# CaravanPi_V3.net
KiCad netlist of a schematic drawn in EAGLE
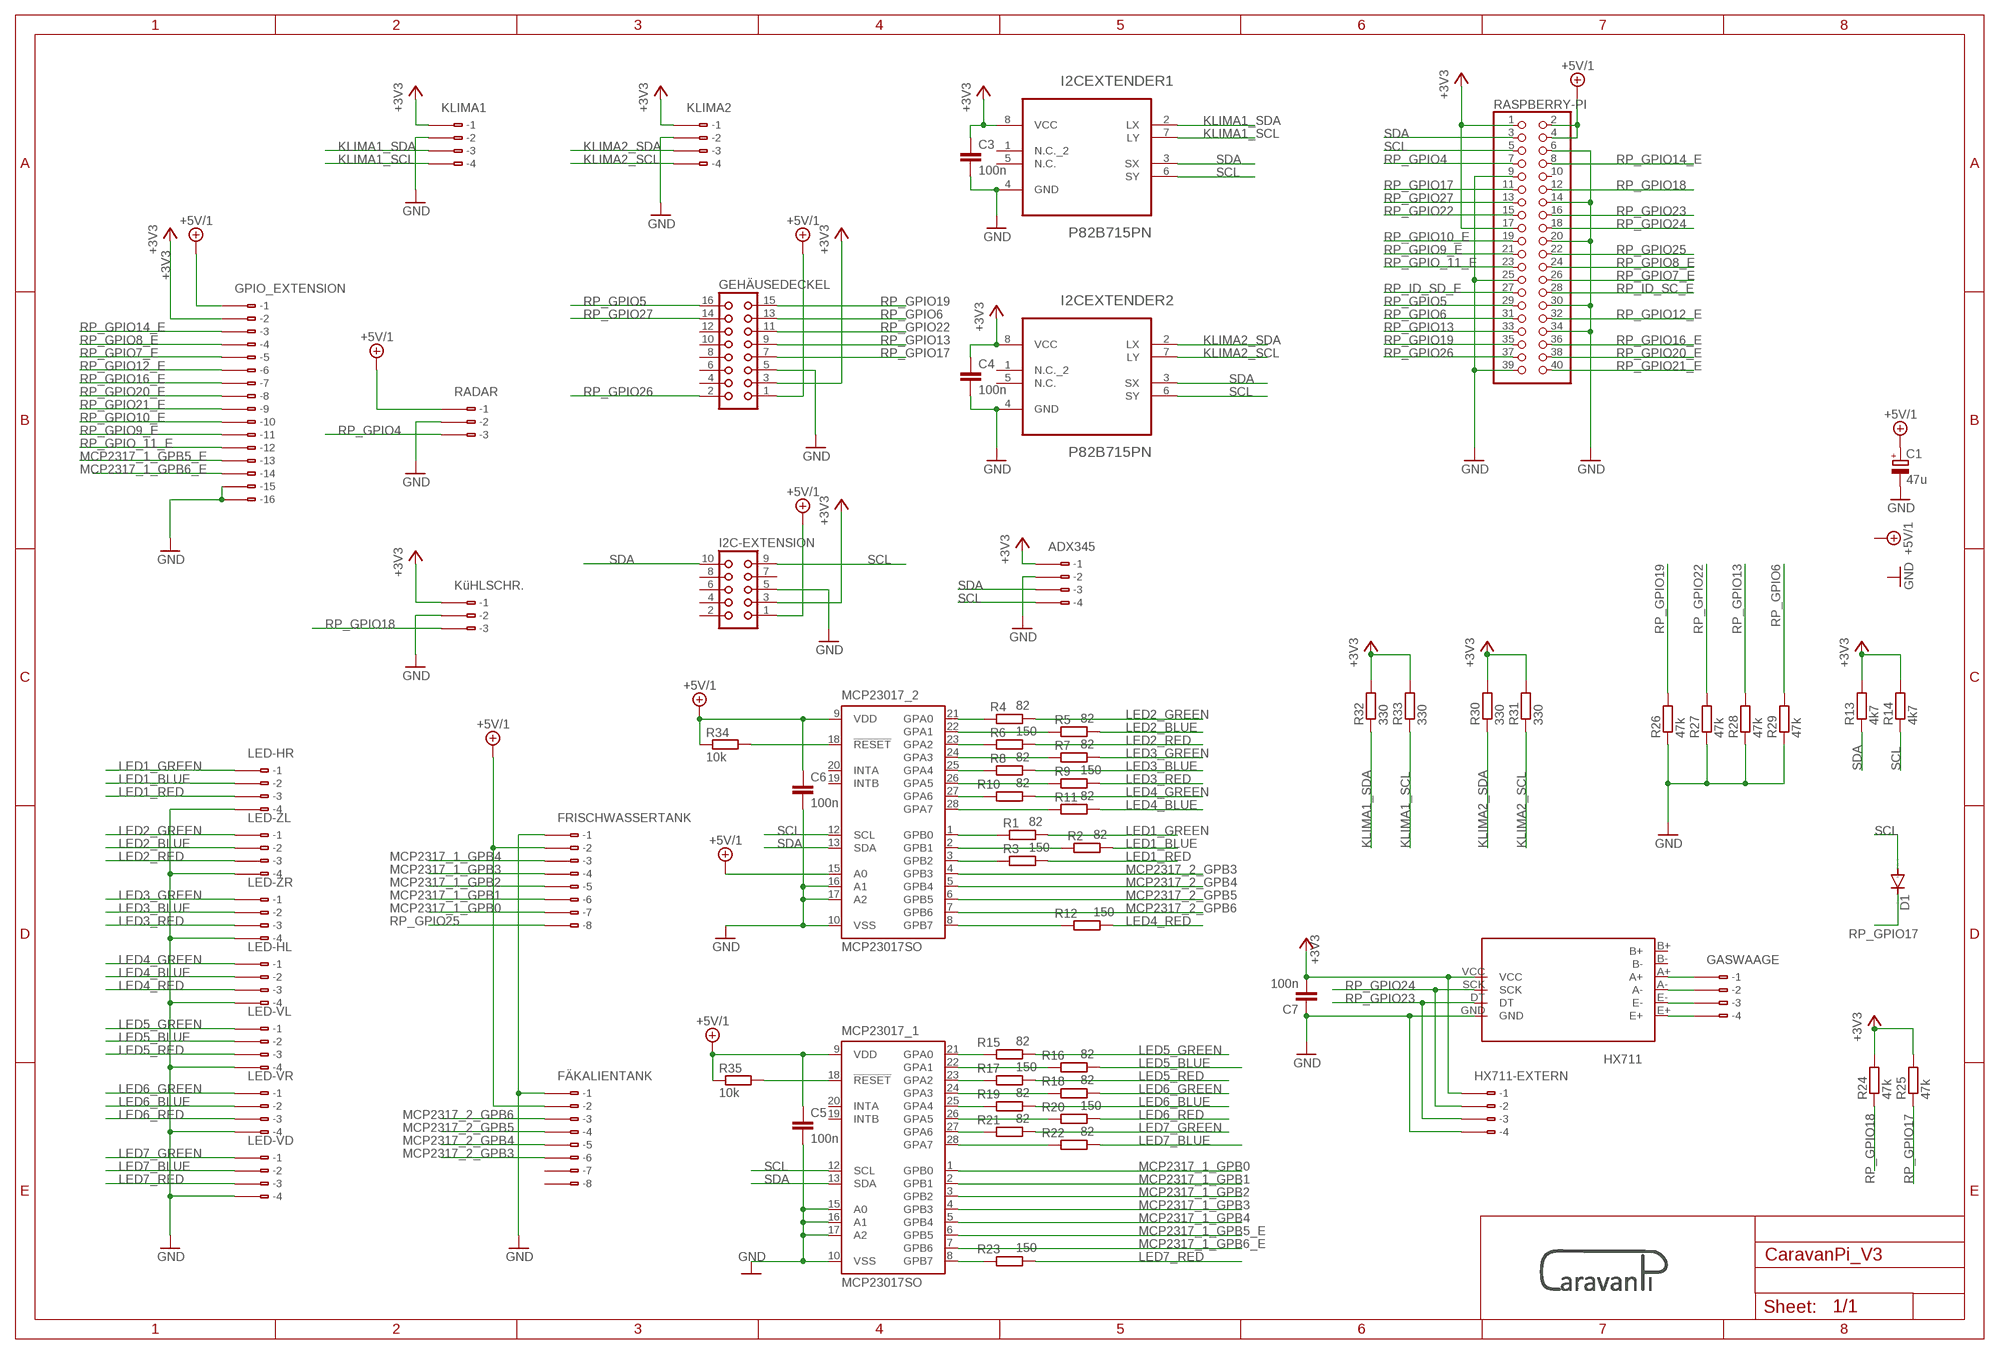
[diagram p0: schematic, sheet 1]

(export (version "E")
  (design (tool "Eeschema 10.0.6"))
  (components
    (comp (ref "ADX345")
      (value "233-404")
      (footprint "eagle-import:233-404")
      (libsource (lib "eagle-import") (part "233-404"))
    )
    (comp (ref "C1")
      (value "47u")
      (footprint "eagle-import:SMC_C")
      (libsource (lib "eagle-import") (part "CPOL-EUSMCC"))
    )
    (comp (ref "C3")
      (value "100n")
      (footprint "eagle-import:C1206")
      (libsource (lib "eagle-import") (part "C-EUC1206"))
    )
    (comp (ref "C4")
      (value "100n")
      (footprint "eagle-import:C1206")
      (libsource (lib "eagle-import") (part "C-EUC1206"))
    )
    (comp (ref "C5")
      (value "100n")
      (footprint "eagle-import:C1206")
      (libsource (lib "eagle-import") (part "C-EUC1206"))
    )
    (comp (ref "C6")
      (value "100n")
      (footprint "eagle-import:C1206")
      (libsource (lib "eagle-import") (part "C-EUC1206"))
    )
    (comp (ref "C7")
      (value "100n")
      (footprint "eagle-import:C1206")
      (libsource (lib "eagle-import") (part "C-EUC1206"))
    )
    (comp (ref "D1")
      (value "DIODE-DO214AC")
      (footprint "eagle-import:DO214AC")
      (libsource (lib "eagle-import") (part "DIODE-DO214AC"))
    )
    (comp (ref "FRISCHWASSERTANK")
      (value "233-408")
      (footprint "eagle-import:233-408")
      (libsource (lib "eagle-import") (part "233-408"))
    )
    (comp (ref "FÄKALIENTANK")
      (value "233-408")
      (footprint "eagle-import:233-408")
      (libsource (lib "eagle-import") (part "233-408"))
    )
    (comp (ref "GASWAAGE")
      (value "233-404")
      (footprint "eagle-import:233-404")
      (libsource (lib "eagle-import") (part "233-404"))
    )
    (comp (ref "GEHÄUSEDECKEL")
      (value "CON16")
      (footprint "eagle-import:CON16")
      (libsource (lib "eagle-import") (part "CON16"))
    )
    (comp (ref "GPIO_EXTENSION")
      (value "233-516")
      (footprint "eagle-import:233-516")
      (fields (field (name "MF") "Wago Corporation") (field (name "MPN") "0233-0516"))
      (libsource (lib "eagle-import") (part "233-516"))
    )
    (comp (ref "HX711")
      (value "HX711A")
      (footprint "eagle-import:HX711")
      (libsource (lib "eagle-import") (part "HX711A"))
    )
    (comp (ref "HX711-EXTERN")
      (value "233-404")
      (footprint "eagle-import:233-404")
      (libsource (lib "eagle-import") (part "233-404"))
    )
    (comp (ref "I2C-EXTENSION")
      (value "CON10")
      (footprint "eagle-import:CON10")
      (libsource (lib "eagle-import") (part "CON10"))
    )
    (comp (ref "I2CEXTENDER1")
      (value "P82B715PN")
      (footprint "eagle-import:DIP254P762X420-8")
      (libsource (lib "eagle-import") (part "P82B715PN"))
    )
    (comp (ref "I2CEXTENDER2")
      (value "P82B715PN")
      (footprint "eagle-import:DIP254P762X420-8")
      (libsource (lib "eagle-import") (part "P82B715PN"))
    )
    (comp (ref "KLIMA1")
      (value "233-404")
      (footprint "eagle-import:233-404")
      (libsource (lib "eagle-import") (part "233-404"))
    )
    (comp (ref "KLIMA2")
      (value "233-404")
      (footprint "eagle-import:233-404")
      (libsource (lib "eagle-import") (part "233-404"))
    )
    (comp (ref "KüHLSCHR.")
      (value "233-403")
      (footprint "eagle-import:233-403")
      (libsource (lib "eagle-import") (part "233-403"))
    )
    (comp (ref "LED-HL")
      (value "233-504")
      (footprint "eagle-import:233-504")
      (fields (field (name "MF") "Wago Corporation") (field (name "MPN") "0233-0504"))
      (libsource (lib "eagle-import") (part "233-504"))
    )
    (comp (ref "LED-HR")
      (value "233-504")
      (footprint "eagle-import:233-504")
      (fields (field (name "MF") "Wago Corporation") (field (name "MPN") "0233-0504"))
      (libsource (lib "eagle-import") (part "233-504"))
    )
    (comp (ref "LED-VD")
      (value "233-504")
      (footprint "eagle-import:233-504")
      (fields (field (name "MF") "Wago Corporation") (field (name "MPN") "0233-0504"))
      (libsource (lib "eagle-import") (part "233-504"))
    )
    (comp (ref "LED-VL")
      (value "233-504")
      (footprint "eagle-import:233-504")
      (fields (field (name "MF") "Wago Corporation") (field (name "MPN") "0233-0504"))
      (libsource (lib "eagle-import") (part "233-504"))
    )
    (comp (ref "LED-VR")
      (value "233-504")
      (footprint "eagle-import:233-504")
      (fields (field (name "MF") "Wago Corporation") (field (name "MPN") "0233-0504"))
      (libsource (lib "eagle-import") (part "233-504"))
    )
    (comp (ref "LED-ZL")
      (value "233-504")
      (footprint "eagle-import:233-504")
      (fields (field (name "MF") "Wago Corporation") (field (name "MPN") "0233-0504"))
      (libsource (lib "eagle-import") (part "233-504"))
    )
    (comp (ref "LED-ZR")
      (value "233-504")
      (footprint "eagle-import:233-504")
      (fields (field (name "MF") "Wago Corporation") (field (name "MPN") "0233-0504"))
      (libsource (lib "eagle-import") (part "233-504"))
    )
    (comp (ref "MCP23017_1")
      (value "MCP23017SO")
      (footprint "eagle-import:SO28W")
      (libsource (lib "eagle-import") (part "MCP23017SO"))
    )
    (comp (ref "MCP23017_2")
      (value "MCP23017SO")
      (footprint "eagle-import:SO28W")
      (libsource (lib "eagle-import") (part "MCP23017SO"))
    )
    (comp (ref "R1")
      (value "82")
      (footprint "eagle-import:M1206")
      (libsource (lib "eagle-import") (part "R-EU_M1206"))
    )
    (comp (ref "R2")
      (value "82")
      (footprint "eagle-import:M1206")
      (libsource (lib "eagle-import") (part "R-EU_M1206"))
    )
    (comp (ref "R3")
      (value "150")
      (footprint "eagle-import:M1206")
      (libsource (lib "eagle-import") (part "R-EU_M1206"))
    )
    (comp (ref "R4")
      (value "82")
      (footprint "eagle-import:M1206")
      (libsource (lib "eagle-import") (part "R-EU_M1206"))
    )
    (comp (ref "R5")
      (value "82")
      (footprint "eagle-import:M1206")
      (libsource (lib "eagle-import") (part "R-EU_M1206"))
    )
    (comp (ref "R6")
      (value "150")
      (footprint "eagle-import:M1206")
      (libsource (lib "eagle-import") (part "R-EU_M1206"))
    )
    (comp (ref "R7")
      (value "82")
      (footprint "eagle-import:M1206")
      (libsource (lib "eagle-import") (part "R-EU_M1206"))
    )
    (comp (ref "R8")
      (value "82")
      (footprint "eagle-import:M1206")
      (libsource (lib "eagle-import") (part "R-EU_M1206"))
    )
    (comp (ref "R9")
      (value "150")
      (footprint "eagle-import:M1206")
      (libsource (lib "eagle-import") (part "R-EU_M1206"))
    )
    (comp (ref "R10")
      (value "82")
      (footprint "eagle-import:M1206")
      (libsource (lib "eagle-import") (part "R-EU_M1206"))
    )
    (comp (ref "R11")
      (value "82")
      (footprint "eagle-import:M1206")
      (libsource (lib "eagle-import") (part "R-EU_M1206"))
    )
    (comp (ref "R12")
      (value "150")
      (footprint "eagle-import:M1206")
      (libsource (lib "eagle-import") (part "R-EU_M1206"))
    )
    (comp (ref "R13")
      (value "4k7")
      (footprint "eagle-import:M1206")
      (libsource (lib "eagle-import") (part "R-EU_M1206"))
    )
    (comp (ref "R14")
      (value "4k7")
      (footprint "eagle-import:M1206")
      (libsource (lib "eagle-import") (part "R-EU_M1206"))
    )
    (comp (ref "R15")
      (value "82")
      (footprint "eagle-import:M1206")
      (libsource (lib "eagle-import") (part "R-EU_M1206"))
    )
    (comp (ref "R16")
      (value "82")
      (footprint "eagle-import:M1206")
      (libsource (lib "eagle-import") (part "R-EU_M1206"))
    )
    (comp (ref "R17")
      (value "150")
      (footprint "eagle-import:M1206")
      (libsource (lib "eagle-import") (part "R-EU_M1206"))
    )
    (comp (ref "R18")
      (value "82")
      (footprint "eagle-import:M1206")
      (libsource (lib "eagle-import") (part "R-EU_M1206"))
    )
    (comp (ref "R19")
      (value "82")
      (footprint "eagle-import:M1206")
      (libsource (lib "eagle-import") (part "R-EU_M1206"))
    )
    (comp (ref "R20")
      (value "150")
      (footprint "eagle-import:M1206")
      (libsource (lib "eagle-import") (part "R-EU_M1206"))
    )
    (comp (ref "R21")
      (value "82")
      (footprint "eagle-import:M1206")
      (libsource (lib "eagle-import") (part "R-EU_M1206"))
    )
    (comp (ref "R22")
      (value "82")
      (footprint "eagle-import:M1206")
      (libsource (lib "eagle-import") (part "R-EU_M1206"))
    )
    (comp (ref "R23")
      (value "150")
      (footprint "eagle-import:M1206")
      (libsource (lib "eagle-import") (part "R-EU_M1206"))
    )
    (comp (ref "R24")
      (value "47k")
      (footprint "eagle-import:M1206")
      (libsource (lib "eagle-import") (part "R-EU_M1206"))
    )
    (comp (ref "R25")
      (value "47k")
      (footprint "eagle-import:M1206")
      (libsource (lib "eagle-import") (part "R-EU_M1206"))
    )
    (comp (ref "R26")
      (value "47k")
      (footprint "eagle-import:M1206")
      (libsource (lib "eagle-import") (part "R-EU_M1206"))
    )
    (comp (ref "R27")
      (value "47k")
      (footprint "eagle-import:M1206")
      (libsource (lib "eagle-import") (part "R-EU_M1206"))
    )
    (comp (ref "R28")
      (value "47k")
      (footprint "eagle-import:M1206")
      (libsource (lib "eagle-import") (part "R-EU_M1206"))
    )
    (comp (ref "R29")
      (value "47k")
      (footprint "eagle-import:M1206")
      (libsource (lib "eagle-import") (part "R-EU_M1206"))
    )
    (comp (ref "R30")
      (value "330")
      (footprint "eagle-import:M1206")
      (libsource (lib "eagle-import") (part "R-EU_M1206"))
    )
    (comp (ref "R31")
      (value "330")
      (footprint "eagle-import:M1206")
      (libsource (lib "eagle-import") (part "R-EU_M1206"))
    )
    (comp (ref "R32")
      (value "330")
      (footprint "eagle-import:M1206")
      (libsource (lib "eagle-import") (part "R-EU_M1206"))
    )
    (comp (ref "R33")
      (value "330")
      (footprint "eagle-import:M1206")
      (libsource (lib "eagle-import") (part "R-EU_M1206"))
    )
    (comp (ref "R34")
      (value "10k")
      (footprint "eagle-import:M1206")
      (libsource (lib "eagle-import") (part "R-EU_M1206"))
    )
    (comp (ref "R35")
      (value "10k")
      (footprint "eagle-import:M1206")
      (libsource (lib "eagle-import") (part "R-EU_M1206"))
    )
    (comp (ref "RADAR")
      (value "233-403")
      (footprint "eagle-import:233-403")
      (libsource (lib "eagle-import") (part "233-403"))
    )
    (comp (ref "RASPBERRY-PI")
      (value "PINHD-2X20")
      (footprint "eagle-import:2X20")
      (libsource (lib "eagle-import") (part "PINHD-2X20"))
    )
    (comp (ref "U$1")
      (value "CARAVAN_PI_LOGO")
      (footprint "eagle-import:CARAVAN_PI_LOGO")
      (libsource (lib "eagle-import") (part "CARAVAN_PI_LOGO"))
    )
  )
  (nets
    (net (code "1") (name "+3V3") (class "Default")
      (node (ref "ADX345") (pin "B1") (pinfunction "B-1_B1") (pintype "passive"))
      (node (ref "C3") (pin "1") (pinfunction "1_1") (pintype "passive"))
      (node (ref "C4") (pin "1") (pinfunction "1_1") (pintype "passive"))
      (node (ref "C7") (pin "2") (pinfunction "2_2") (pintype "passive"))
      (node (ref "GEHÄUSEDECKEL") (pin "3") (pinfunction "3_3") (pintype "passive"))
      (node (ref "GPIO_EXTENSION") (pin "B2") (pinfunction "B-2_B2") (pintype "passive"))
      (node (ref "HX711") (pin "VCC") (pinfunction "VCC_VCC") (pintype "bidirectional"))
      (node (ref "HX711-EXTERN") (pin "B1") (pinfunction "B-1_B1") (pintype "passive"))
      (node (ref "I2C-EXTENSION") (pin "3") (pinfunction "3_3") (pintype "passive"))
      (node (ref "I2CEXTENDER1") (pin "8") (pinfunction "VCC_8") (pintype "power_in"))
      (node (ref "I2CEXTENDER2") (pin "8") (pinfunction "VCC_8") (pintype "power_in"))
      (node (ref "KLIMA1") (pin "B1") (pinfunction "B-1_B1") (pintype "passive"))
      (node (ref "KLIMA2") (pin "B1") (pinfunction "B-1_B1") (pintype "passive"))
      (node (ref "KüHLSCHR.") (pin "B1") (pinfunction "B-1_B1") (pintype "passive"))
      (node (ref "R13") (pin "2") (pinfunction "2_2") (pintype "passive"))
      (node (ref "R14") (pin "2") (pinfunction "2_2") (pintype "passive"))
      (node (ref "R24") (pin "2") (pinfunction "2_2") (pintype "passive"))
      (node (ref "R25") (pin "2") (pinfunction "2_2") (pintype "passive"))
      (node (ref "R30") (pin "2") (pinfunction "2_2") (pintype "passive"))
      (node (ref "R31") (pin "2") (pinfunction "2_2") (pintype "passive"))
      (node (ref "R32") (pin "2") (pinfunction "2_2") (pintype "passive"))
      (node (ref "R33") (pin "2") (pinfunction "2_2") (pintype "passive"))
      (node (ref "RASPBERRY-PI") (pin "1") (pinfunction "1_1") (pintype "passive"))
      (node (ref "RASPBERRY-PI") (pin "17") (pinfunction "17_17") (pintype "passive"))
    )
    (net (code "2") (name "+5V{slash}1") (class "Default")
      (node (ref "C1") (pin "+") (pinfunction "+_+") (pintype "passive"))
      (node (ref "C5") (pin "1") (pinfunction "1_1") (pintype "passive"))
      (node (ref "C6") (pin "1") (pinfunction "1_1") (pintype "passive"))
      (node (ref "FRISCHWASSERTANK") (pin "B2") (pinfunction "B-2_B2") (pintype "passive"))
      (node (ref "FÄKALIENTANK") (pin "B2") (pinfunction "B-2_B2") (pintype "passive"))
      (node (ref "GEHÄUSEDECKEL") (pin "1") (pinfunction "1_1") (pintype "passive"))
      (node (ref "GPIO_EXTENSION") (pin "B1") (pinfunction "B-1_B1") (pintype "passive"))
      (node (ref "I2C-EXTENSION") (pin "1") (pinfunction "1_1") (pintype "passive"))
      (node (ref "MCP23017_1") (pin "9") (pinfunction "VDD_9") (pintype "power_in"))
      (node (ref "MCP23017_2") (pin "15") (pinfunction "A0_15") (pintype "input"))
      (node (ref "MCP23017_2") (pin "9") (pinfunction "VDD_9") (pintype "power_in"))
      (node (ref "R34") (pin "1") (pinfunction "1_1") (pintype "passive"))
      (node (ref "R35") (pin "1") (pinfunction "1_1") (pintype "passive"))
      (node (ref "RADAR") (pin "B1") (pinfunction "B-1_B1") (pintype "passive"))
      (node (ref "RASPBERRY-PI") (pin "2") (pinfunction "2_2") (pintype "passive"))
      (node (ref "RASPBERRY-PI") (pin "4") (pinfunction "4_4") (pintype "passive"))
    )
    (net (code "3") (name "/KLIMA1_SCL") (class "Default")
      (node (ref "I2CEXTENDER1") (pin "7") (pinfunction "LY_7") (pintype "bidirectional"))
      (node (ref "KLIMA1") (pin "B4") (pinfunction "B-4_B4") (pintype "passive"))
      (node (ref "R33") (pin "1") (pinfunction "1_1") (pintype "passive"))
    )
    (net (code "4") (name "/KLIMA1_SDA") (class "Default")
      (node (ref "I2CEXTENDER1") (pin "2") (pinfunction "LX_2") (pintype "bidirectional"))
      (node (ref "KLIMA1") (pin "B3") (pinfunction "B-3_B3") (pintype "passive"))
      (node (ref "R32") (pin "1") (pinfunction "1_1") (pintype "passive"))
    )
    (net (code "5") (name "/KLIMA2_SCL") (class "Default")
      (node (ref "I2CEXTENDER2") (pin "7") (pinfunction "LY_7") (pintype "bidirectional"))
      (node (ref "KLIMA2") (pin "B4") (pinfunction "B-4_B4") (pintype "passive"))
      (node (ref "R31") (pin "1") (pinfunction "1_1") (pintype "passive"))
    )
    (net (code "6") (name "/KLIMA2_SDA") (class "Default")
      (node (ref "I2CEXTENDER2") (pin "2") (pinfunction "LX_2") (pintype "bidirectional"))
      (node (ref "KLIMA2") (pin "B3") (pinfunction "B-3_B3") (pintype "passive"))
      (node (ref "R30") (pin "1") (pinfunction "1_1") (pintype "passive"))
    )
    (net (code "7") (name "/LED1_BLUE") (class "Default")
      (node (ref "LED-HR") (pin "B2") (pinfunction "B-2_B2") (pintype "passive"))
      (node (ref "R2") (pin "2") (pinfunction "2_2") (pintype "passive"))
    )
    (net (code "8") (name "/LED1_GREEN") (class "Default")
      (node (ref "LED-HR") (pin "B1") (pinfunction "B-1_B1") (pintype "passive"))
      (node (ref "R1") (pin "2") (pinfunction "2_2") (pintype "passive"))
    )
    (net (code "9") (name "/LED1_RED") (class "Default")
      (node (ref "LED-HR") (pin "B3") (pinfunction "B-3_B3") (pintype "passive"))
      (node (ref "R3") (pin "2") (pinfunction "2_2") (pintype "passive"))
    )
    (net (code "10") (name "/LED2_BLUE") (class "Default")
      (node (ref "LED-ZL") (pin "B2") (pinfunction "B-2_B2") (pintype "passive"))
      (node (ref "R5") (pin "2") (pinfunction "2_2") (pintype "passive"))
    )
    (net (code "11") (name "/LED2_GREEN") (class "Default")
      (node (ref "LED-ZL") (pin "B1") (pinfunction "B-1_B1") (pintype "passive"))
      (node (ref "R4") (pin "2") (pinfunction "2_2") (pintype "passive"))
    )
    (net (code "12") (name "/LED2_RED") (class "Default")
      (node (ref "LED-ZL") (pin "B3") (pinfunction "B-3_B3") (pintype "passive"))
      (node (ref "R6") (pin "2") (pinfunction "2_2") (pintype "passive"))
    )
    (net (code "13") (name "/LED3_BLUE") (class "Default")
      (node (ref "LED-ZR") (pin "B2") (pinfunction "B-2_B2") (pintype "passive"))
      (node (ref "R8") (pin "2") (pinfunction "2_2") (pintype "passive"))
    )
    (net (code "14") (name "/LED3_GREEN") (class "Default")
      (node (ref "LED-ZR") (pin "B1") (pinfunction "B-1_B1") (pintype "passive"))
      (node (ref "R7") (pin "2") (pinfunction "2_2") (pintype "passive"))
    )
    (net (code "15") (name "/LED3_RED") (class "Default")
      (node (ref "LED-ZR") (pin "B3") (pinfunction "B-3_B3") (pintype "passive"))
      (node (ref "R9") (pin "2") (pinfunction "2_2") (pintype "passive"))
    )
    (net (code "16") (name "/LED4_BLUE") (class "Default")
      (node (ref "LED-HL") (pin "B2") (pinfunction "B-2_B2") (pintype "passive"))
      (node (ref "R11") (pin "2") (pinfunction "2_2") (pintype "passive"))
    )
    (net (code "17") (name "/LED4_GREEN") (class "Default")
      (node (ref "LED-HL") (pin "B1") (pinfunction "B-1_B1") (pintype "passive"))
      (node (ref "R10") (pin "2") (pinfunction "2_2") (pintype "passive"))
    )
    (net (code "18") (name "/LED4_RED") (class "Default")
      (node (ref "LED-HL") (pin "B3") (pinfunction "B-3_B3") (pintype "passive"))
      (node (ref "R12") (pin "2") (pinfunction "2_2") (pintype "passive"))
    )
    (net (code "19") (name "/LED5_BLUE") (class "Default")
      (node (ref "LED-VL") (pin "B2") (pinfunction "B-2_B2") (pintype "passive"))
      (node (ref "R16") (pin "2") (pinfunction "2_2") (pintype "passive"))
    )
    (net (code "20") (name "/LED5_GREEN") (class "Default")
      (node (ref "LED-VL") (pin "B1") (pinfunction "B-1_B1") (pintype "passive"))
      (node (ref "R15") (pin "2") (pinfunction "2_2") (pintype "passive"))
    )
    (net (code "21") (name "/LED5_RED") (class "Default")
      (node (ref "LED-VL") (pin "B3") (pinfunction "B-3_B3") (pintype "passive"))
      (node (ref "R17") (pin "2") (pinfunction "2_2") (pintype "passive"))
    )
    (net (code "22") (name "/LED6_BLUE") (class "Default")
      (node (ref "LED-VR") (pin "B2") (pinfunction "B-2_B2") (pintype "passive"))
      (node (ref "R19") (pin "2") (pinfunction "2_2") (pintype "passive"))
    )
    (net (code "23") (name "/LED6_GREEN") (class "Default")
      (node (ref "LED-VR") (pin "B1") (pinfunction "B-1_B1") (pintype "passive"))
      (node (ref "R18") (pin "2") (pinfunction "2_2") (pintype "passive"))
    )
    (net (code "24") (name "/LED6_RED") (class "Default")
      (node (ref "LED-VR") (pin "B3") (pinfunction "B-3_B3") (pintype "passive"))
      (node (ref "R20") (pin "2") (pinfunction "2_2") (pintype "passive"))
    )
    (net (code "25") (name "/LED7_BLUE") (class "Default")
      (node (ref "LED-VD") (pin "B2") (pinfunction "B-2_B2") (pintype "passive"))
      (node (ref "R22") (pin "2") (pinfunction "2_2") (pintype "passive"))
    )
    (net (code "26") (name "/LED7_GREEN") (class "Default")
      (node (ref "LED-VD") (pin "B1") (pinfunction "B-1_B1") (pintype "passive"))
      (node (ref "R21") (pin "2") (pinfunction "2_2") (pintype "passive"))
    )
    (net (code "27") (name "/LED7_RED") (class "Default")
      (node (ref "LED-VD") (pin "B3") (pinfunction "B-3_B3") (pintype "passive"))
      (node (ref "R23") (pin "2") (pinfunction "2_2") (pintype "passive"))
    )
    (net (code "28") (name "/MCP2317_1_GPB0") (class "Default")
      (node (ref "FRISCHWASSERTANK") (pin "B7") (pinfunction "B-7_B7") (pintype "passive"))
      (node (ref "MCP23017_1") (pin "1") (pinfunction "GPB0_1") (pintype "bidirectional"))
    )
    (net (code "29") (name "/MCP2317_1_GPB1") (class "Default")
      (node (ref "FRISCHWASSERTANK") (pin "B6") (pinfunction "B-6_B6") (pintype "passive"))
      (node (ref "MCP23017_1") (pin "2") (pinfunction "GPB1_2") (pintype "bidirectional"))
    )
    (net (code "30") (name "/MCP2317_1_GPB2") (class "Default")
      (node (ref "FRISCHWASSERTANK") (pin "B5") (pinfunction "B-5_B5") (pintype "passive"))
      (node (ref "MCP23017_1") (pin "3") (pinfunction "GPB2_3") (pintype "bidirectional"))
    )
    (net (code "31") (name "/MCP2317_1_GPB3") (class "Default")
      (node (ref "FRISCHWASSERTANK") (pin "B4") (pinfunction "B-4_B4") (pintype "passive"))
      (node (ref "MCP23017_1") (pin "4") (pinfunction "GPB3_4") (pintype "bidirectional"))
    )
    (net (code "32") (name "/MCP2317_1_GPB4") (class "Default")
      (node (ref "FRISCHWASSERTANK") (pin "B3") (pinfunction "B-3_B3") (pintype "passive"))
      (node (ref "MCP23017_1") (pin "5") (pinfunction "GPB4_5") (pintype "bidirectional"))
    )
    (net (code "33") (name "/MCP2317_1_GPB5_E") (class "Default")
      (node (ref "GPIO_EXTENSION") (pin "B13") (pinfunction "B-13_B13") (pintype "passive"))
      (node (ref "MCP23017_1") (pin "6") (pinfunction "GPB5_6") (pintype "bidirectional"))
    )
    (net (code "34") (name "/MCP2317_1_GPB6_E") (class "Default")
      (node (ref "GPIO_EXTENSION") (pin "B14") (pinfunction "B-14_B14") (pintype "passive"))
      (node (ref "MCP23017_1") (pin "7") (pinfunction "GPB6_7") (pintype "bidirectional"))
    )
    (net (code "35") (name "/MCP2317_2_GPB3") (class "Default")
      (node (ref "FÄKALIENTANK") (pin "B6") (pinfunction "B-6_B6") (pintype "passive"))
      (node (ref "MCP23017_2") (pin "4") (pinfunction "GPB3_4") (pintype "bidirectional"))
    )
    (net (code "36") (name "/MCP2317_2_GPB4") (class "Default")
      (node (ref "FÄKALIENTANK") (pin "B5") (pinfunction "B-5_B5") (pintype "passive"))
      (node (ref "MCP23017_2") (pin "5") (pinfunction "GPB4_5") (pintype "bidirectional"))
    )
    (net (code "37") (name "/MCP2317_2_GPB5") (class "Default")
      (node (ref "FÄKALIENTANK") (pin "B4") (pinfunction "B-4_B4") (pintype "passive"))
      (node (ref "MCP23017_2") (pin "6") (pinfunction "GPB5_6") (pintype "bidirectional"))
    )
    (net (code "38") (name "/MCP2317_2_GPB6") (class "Default")
      (node (ref "FÄKALIENTANK") (pin "B3") (pinfunction "B-3_B3") (pintype "passive"))
      (node (ref "MCP23017_2") (pin "7") (pinfunction "GPB6_7") (pintype "bidirectional"))
    )
    (net (code "39") (name "/RP_GPIO4") (class "Default")
      (node (ref "RADAR") (pin "B3") (pinfunction "B-3_B3") (pintype "passive"))
      (node (ref "RASPBERRY-PI") (pin "7") (pinfunction "7_7") (pintype "passive"))
    )
    (net (code "40") (name "/RP_GPIO5") (class "Default")
      (node (ref "GEHÄUSEDECKEL") (pin "16") (pinfunction "16_16") (pintype "passive"))
      (node (ref "RASPBERRY-PI") (pin "29") (pinfunction "29_29") (pintype "passive"))
    )
    (net (code "41") (name "/RP_GPIO6") (class "Default")
      (node (ref "GEHÄUSEDECKEL") (pin "13") (pinfunction "13_13") (pintype "passive"))
      (node (ref "R29") (pin "2") (pinfunction "2_2") (pintype "passive"))
      (node (ref "RASPBERRY-PI") (pin "31") (pinfunction "31_31") (pintype "passive"))
    )
    (net (code "42") (name "/RP_GPIO7_E") (class "Default")
      (node (ref "GPIO_EXTENSION") (pin "B5") (pinfunction "B-5_B5") (pintype "passive"))
      (node (ref "RASPBERRY-PI") (pin "26") (pinfunction "26_26") (pintype "passive"))
    )
    (net (code "43") (name "/RP_GPIO8_E") (class "Default")
      (node (ref "GPIO_EXTENSION") (pin "B4") (pinfunction "B-4_B4") (pintype "passive"))
      (node (ref "RASPBERRY-PI") (pin "24") (pinfunction "24_24") (pintype "passive"))
    )
    (net (code "44") (name "/RP_GPIO9_E") (class "Default")
      (node (ref "GPIO_EXTENSION") (pin "B11") (pinfunction "B-11_B11") (pintype "passive"))
      (node (ref "RASPBERRY-PI") (pin "21") (pinfunction "21_21") (pintype "passive"))
    )
    (net (code "45") (name "/RP_GPIO10_E") (class "Default")
      (node (ref "GPIO_EXTENSION") (pin "B10") (pinfunction "B-10_B10") (pintype "passive"))
      (node (ref "RASPBERRY-PI") (pin "19") (pinfunction "19_19") (pintype "passive"))
    )
    (net (code "46") (name "/RP_GPIO12_E") (class "Default")
      (node (ref "GPIO_EXTENSION") (pin "B6") (pinfunction "B-6_B6") (pintype "passive"))
      (node (ref "RASPBERRY-PI") (pin "32") (pinfunction "32_32") (pintype "passive"))
    )
    (net (code "47") (name "/RP_GPIO13") (class "Default")
      (node (ref "GEHÄUSEDECKEL") (pin "9") (pinfunction "9_9") (pintype "passive"))
      (node (ref "R28") (pin "2") (pinfunction "2_2") (pintype "passive"))
      (node (ref "RASPBERRY-PI") (pin "33") (pinfunction "33_33") (pintype "passive"))
    )
    (net (code "48") (name "/RP_GPIO14_E") (class "Default")
      (node (ref "GPIO_EXTENSION") (pin "B3") (pinfunction "B-3_B3") (pintype "passive"))
      (node (ref "RASPBERRY-PI") (pin "8") (pinfunction "8_8") (pintype "passive"))
    )
    (net (code "49") (name "/RP_GPIO16_E") (class "Default")
      (node (ref "GPIO_EXTENSION") (pin "B7") (pinfunction "B-7_B7") (pintype "passive"))
      (node (ref "RASPBERRY-PI") (pin "36") (pinfunction "36_36") (pintype "passive"))
    )
    (net (code "50") (name "/RP_GPIO17") (class "Default")
      (node (ref "D1") (pin "C") (pinfunction "C_C") (pintype "passive"))
      (node (ref "GEHÄUSEDECKEL") (pin "7") (pinfunction "7_7") (pintype "passive"))
      (node (ref "R25") (pin "1") (pinfunction "1_1") (pintype "passive"))
      (node (ref "RASPBERRY-PI") (pin "11") (pinfunction "11_11") (pintype "passive"))
    )
    (net (code "51") (name "/RP_GPIO18") (class "Default")
      (node (ref "KüHLSCHR.") (pin "B3") (pinfunction "B-3_B3") (pintype "passive"))
      (node (ref "R24") (pin "1") (pinfunction "1_1") (pintype "passive"))
      (node (ref "RASPBERRY-PI") (pin "12") (pinfunction "12_12") (pintype "passive"))
    )
    (net (code "52") (name "/RP_GPIO19") (class "Default")
      (node (ref "GEHÄUSEDECKEL") (pin "15") (pinfunction "15_15") (pintype "passive"))
      (node (ref "R26") (pin "2") (pinfunction "2_2") (pintype "passive"))
      (node (ref "RASPBERRY-PI") (pin "35") (pinfunction "35_35") (pintype "passive"))
    )
    (net (code "53") (name "/RP_GPIO20_E") (class "Default")
      (node (ref "GPIO_EXTENSION") (pin "B8") (pinfunction "B-8_B8") (pintype "passive"))
      (node (ref "RASPBERRY-PI") (pin "38") (pinfunction "38_38") (pintype "passive"))
    )
    (net (code "54") (name "/RP_GPIO21_E") (class "Default")
      (node (ref "GPIO_EXTENSION") (pin "B9") (pinfunction "B-9_B9") (pintype "passive"))
      (node (ref "RASPBERRY-PI") (pin "40") (pinfunction "40_40") (pintype "passive"))
    )
    (net (code "55") (name "/RP_GPIO22") (class "Default")
      (node (ref "GEHÄUSEDECKEL") (pin "11") (pinfunction "11_11") (pintype "passive"))
      (node (ref "R27") (pin "2") (pinfunction "2_2") (pintype "passive"))
      (node (ref "RASPBERRY-PI") (pin "15") (pinfunction "15_15") (pintype "passive"))
    )
    (net (code "56") (name "/RP_GPIO23") (class "Default")
      (node (ref "HX711") (pin "DT") (pinfunction "DT_DT") (pintype "bidirectional"))
      (node (ref "HX711-EXTERN") (pin "B3") (pinfunction "B-3_B3") (pintype "passive"))
      (node (ref "RASPBERRY-PI") (pin "16") (pinfunction "16_16") (pintype "passive"))
    )
    (net (code "57") (name "/RP_GPIO24") (class "Default")
      (node (ref "HX711") (pin "SCK") (pinfunction "SCK_SCK") (pintype "bidirectional"))
      (node (ref "HX711-EXTERN") (pin "B2") (pinfunction "B-2_B2") (pintype "passive"))
      (node (ref "RASPBERRY-PI") (pin "18") (pinfunction "18_18") (pintype "passive"))
    )
    (net (code "58") (name "/RP_GPIO25") (class "Default")
      (node (ref "FRISCHWASSERTANK") (pin "B8") (pinfunction "B-8_B8") (pintype "passive"))
      (node (ref "RASPBERRY-PI") (pin "22") (pinfunction "22_22") (pintype "passive"))
    )
    (net (code "59") (name "/RP_GPIO26") (class "Default")
      (node (ref "GEHÄUSEDECKEL") (pin "2") (pinfunction "2_2") (pintype "passive"))
      (node (ref "RASPBERRY-PI") (pin "37") (pinfunction "37_37") (pintype "passive"))
    )
    (net (code "60") (name "/RP_GPIO27") (class "Default")
      (node (ref "GEHÄUSEDECKEL") (pin "14") (pinfunction "14_14") (pintype "passive"))
      (node (ref "RASPBERRY-PI") (pin "13") (pinfunction "13_13") (pintype "passive"))
    )
    (net (code "61") (name "/RP_GPIO_11_E") (class "Default")
      (node (ref "GPIO_EXTENSION") (pin "B12") (pinfunction "B-12_B12") (pintype "passive"))
      (node (ref "RASPBERRY-PI") (pin "23") (pinfunction "23_23") (pintype "passive"))
    )
    (net (code "62") (name "/RP_ID_SC_E") (class "Default")
      (node (ref "RASPBERRY-PI") (pin "28") (pinfunction "28_28") (pintype "passive"))
    )
    (net (code "63") (name "/RP_ID_SD_E") (class "Default")
      (node (ref "RASPBERRY-PI") (pin "27") (pinfunction "27_27") (pintype "passive"))
    )
    (net (code "64") (name "/SCL") (class "Default")
      (node (ref "ADX345") (pin "B4") (pinfunction "B-4_B4") (pintype "passive"))
      (node (ref "D1") (pin "A") (pinfunction "A_A") (pintype "passive"))
      (node (ref "I2C-EXTENSION") (pin "9") (pinfunction "9_9") (pintype "passive"))
      (node (ref "I2CEXTENDER1") (pin "6") (pinfunction "SY_6") (pintype "bidirectional"))
      (node (ref "I2CEXTENDER2") (pin "6") (pinfunction "SY_6") (pintype "bidirectional"))
      (node (ref "MCP23017_1") (pin "12") (pinfunction "SCL_12") (pintype "input"))
      (node (ref "MCP23017_2") (pin "12") (pinfunction "SCL_12") (pintype "input"))
      (node (ref "R14") (pin "1") (pinfunction "1_1") (pintype "passive"))
      (node (ref "RASPBERRY-PI") (pin "5") (pinfunction "5_5") (pintype "passive"))
    )
    (net (code "65") (name "/SDA") (class "Default")
      (node (ref "ADX345") (pin "B3") (pinfunction "B-3_B3") (pintype "passive"))
      (node (ref "I2C-EXTENSION") (pin "10") (pinfunction "10_10") (pintype "passive"))
      (node (ref "I2CEXTENDER1") (pin "3") (pinfunction "SX_3") (pintype "bidirectional"))
      (node (ref "I2CEXTENDER2") (pin "3") (pinfunction "SX_3") (pintype "bidirectional"))
      (node (ref "MCP23017_1") (pin "13") (pinfunction "SDA_13") (pintype "bidirectional"))
      (node (ref "MCP23017_2") (pin "13") (pinfunction "SDA_13") (pintype "bidirectional"))
      (node (ref "R13") (pin "1") (pinfunction "1_1") (pintype "passive"))
      (node (ref "RASPBERRY-PI") (pin "3") (pinfunction "3_3") (pintype "passive"))
    )
    (net (code "66") (name "GND") (class "Default")
      (node (ref "ADX345") (pin "B2") (pinfunction "B-2_B2") (pintype "passive"))
      (node (ref "C1") (pin "-") (pinfunction "-_-") (pintype "passive"))
      (node (ref "C3") (pin "2") (pinfunction "2_2") (pintype "passive"))
      (node (ref "C4") (pin "2") (pinfunction "2_2") (pintype "passive"))
      (node (ref "C5") (pin "2") (pinfunction "2_2") (pintype "passive"))
      (node (ref "C6") (pin "2") (pinfunction "2_2") (pintype "passive"))
      (node (ref "C7") (pin "1") (pinfunction "1_1") (pintype "passive"))
      (node (ref "FRISCHWASSERTANK") (pin "B1") (pinfunction "B-1_B1") (pintype "passive"))
      (node (ref "FÄKALIENTANK") (pin "B1") (pinfunction "B-1_B1") (pintype "passive"))
      (node (ref "GEHÄUSEDECKEL") (pin "5") (pinfunction "5_5") (pintype "passive"))
      (node (ref "GPIO_EXTENSION") (pin "B15") (pinfunction "B-15_B15") (pintype "passive"))
      (node (ref "GPIO_EXTENSION") (pin "B16") (pinfunction "B-16_B16") (pintype "passive"))
      (node (ref "HX711") (pin "GND") (pinfunction "GND_GND") (pintype "bidirectional"))
      (node (ref "HX711-EXTERN") (pin "B4") (pinfunction "B-4_B4") (pintype "passive"))
      (node (ref "I2C-EXTENSION") (pin "5") (pinfunction "5_5") (pintype "passive"))
      (node (ref "I2CEXTENDER1") (pin "4") (pinfunction "GND_4") (pintype "passive"))
      (node (ref "I2CEXTENDER2") (pin "4") (pinfunction "GND_4") (pintype "passive"))
      (node (ref "KLIMA1") (pin "B2") (pinfunction "B-2_B2") (pintype "passive"))
      (node (ref "KLIMA2") (pin "B2") (pinfunction "B-2_B2") (pintype "passive"))
      (node (ref "KüHLSCHR.") (pin "B2") (pinfunction "B-2_B2") (pintype "passive"))
      (node (ref "LED-HL") (pin "B4") (pinfunction "B-4_B4") (pintype "passive"))
      (node (ref "LED-HR") (pin "B4") (pinfunction "B-4_B4") (pintype "passive"))
      (node (ref "LED-VD") (pin "B4") (pinfunction "B-4_B4") (pintype "passive"))
      (node (ref "LED-VL") (pin "B4") (pinfunction "B-4_B4") (pintype "passive"))
      (node (ref "LED-VR") (pin "B4") (pinfunction "B-4_B4") (pintype "passive"))
      (node (ref "LED-ZL") (pin "B4") (pinfunction "B-4_B4") (pintype "passive"))
      (node (ref "LED-ZR") (pin "B4") (pinfunction "B-4_B4") (pintype "passive"))
      (node (ref "MCP23017_1") (pin "10") (pinfunction "VSS_10") (pintype "power_in"))
      (node (ref "MCP23017_1") (pin "15") (pinfunction "A0_15") (pintype "input"))
      (node (ref "MCP23017_1") (pin "16") (pinfunction "A1_16") (pintype "input"))
      (node (ref "MCP23017_1") (pin "17") (pinfunction "A2_17") (pintype "input"))
      (node (ref "MCP23017_2") (pin "10") (pinfunction "VSS_10") (pintype "power_in"))
      (node (ref "MCP23017_2") (pin "16") (pinfunction "A1_16") (pintype "input"))
      (node (ref "MCP23017_2") (pin "17") (pinfunction "A2_17") (pintype "input"))
      (node (ref "R26") (pin "1") (pinfunction "1_1") (pintype "passive"))
      (node (ref "R27") (pin "1") (pinfunction "1_1") (pintype "passive"))
      (node (ref "R28") (pin "1") (pinfunction "1_1") (pintype "passive"))
      (node (ref "R29") (pin "1") (pinfunction "1_1") (pintype "passive"))
      (node (ref "RADAR") (pin "B2") (pinfunction "B-2_B2") (pintype "passive"))
      (node (ref "RASPBERRY-PI") (pin "14") (pinfunction "14_14") (pintype "passive"))
      (node (ref "RASPBERRY-PI") (pin "20") (pinfunction "20_20") (pintype "passive"))
      (node (ref "RASPBERRY-PI") (pin "25") (pinfunction "25_25") (pintype "passive"))
      (node (ref "RASPBERRY-PI") (pin "30") (pinfunction "30_30") (pintype "passive"))
      (node (ref "RASPBERRY-PI") (pin "34") (pinfunction "34_34") (pintype "passive"))
      (node (ref "RASPBERRY-PI") (pin "39") (pinfunction "39_39") (pintype "passive"))
      (node (ref "RASPBERRY-PI") (pin "6") (pinfunction "6_6") (pintype "passive"))
      (node (ref "RASPBERRY-PI") (pin "9") (pinfunction "9_9") (pintype "passive"))
    )
    (net (code "67") (name "Net-(GASWAAGE-B-1)") (class "Default")
      (node (ref "GASWAAGE") (pin "B1") (pinfunction "B-1_B1") (pintype "passive"))
      (node (ref "HX711") (pin "A+") (pinfunction "A+_A+") (pintype "bidirectional"))
    )
    (net (code "68") (name "Net-(GASWAAGE-B-2)") (class "Default")
      (node (ref "GASWAAGE") (pin "B2") (pinfunction "B-2_B2") (pintype "passive"))
      (node (ref "HX711") (pin "A-") (pinfunction "A-_A-") (pintype "bidirectional"))
    )
    (net (code "69") (name "Net-(GASWAAGE-B-3)") (class "Default")
      (node (ref "GASWAAGE") (pin "B3") (pinfunction "B-3_B3") (pintype "passive"))
      (node (ref "HX711") (pin "E-") (pinfunction "E-_E-") (pintype "bidirectional"))
    )
    (net (code "70") (name "Net-(GASWAAGE-B-4)") (class "Default")
      (node (ref "GASWAAGE") (pin "B4") (pinfunction "B-4_B4") (pintype "passive"))
      (node (ref "HX711") (pin "E+") (pinfunction "E+_E+") (pintype "bidirectional"))
    )
    (net (code "71") (name "Net-(MCP23017_1-GPA0)") (class "Default")
      (node (ref "MCP23017_1") (pin "21") (pinfunction "GPA0_21") (pintype "bidirectional"))
      (node (ref "R15") (pin "1") (pinfunction "1_1") (pintype "passive"))
    )
    (net (code "72") (name "Net-(MCP23017_1-GPA1)") (class "Default")
      (node (ref "MCP23017_1") (pin "22") (pinfunction "GPA1_22") (pintype "bidirectional"))
      (node (ref "R16") (pin "1") (pinfunction "1_1") (pintype "passive"))
    )
    (net (code "73") (name "Net-(MCP23017_1-GPA2)") (class "Default")
      (node (ref "MCP23017_1") (pin "23") (pinfunction "GPA2_23") (pintype "bidirectional"))
      (node (ref "R17") (pin "1") (pinfunction "1_1") (pintype "passive"))
    )
    (net (code "74") (name "Net-(MCP23017_1-GPA3)") (class "Default")
      (node (ref "MCP23017_1") (pin "24") (pinfunction "GPA3_24") (pintype "bidirectional"))
      (node (ref "R18") (pin "1") (pinfunction "1_1") (pintype "passive"))
    )
    (net (code "75") (name "Net-(MCP23017_1-GPA4)") (class "Default")
      (node (ref "MCP23017_1") (pin "25") (pinfunction "GPA4_25") (pintype "bidirectional"))
      (node (ref "R19") (pin "1") (pinfunction "1_1") (pintype "passive"))
    )
    (net (code "76") (name "Net-(MCP23017_1-GPA5)") (class "Default")
      (node (ref "MCP23017_1") (pin "26") (pinfunction "GPA5_26") (pintype "bidirectional"))
      (node (ref "R20") (pin "1") (pinfunction "1_1") (pintype "passive"))
    )
    (net (code "77") (name "Net-(MCP23017_1-GPA6)") (class "Default")
      (node (ref "MCP23017_1") (pin "27") (pinfunction "GPA6_27") (pintype "bidirectional"))
      (node (ref "R21") (pin "1") (pinfunction "1_1") (pintype "passive"))
    )
    (net (code "78") (name "Net-(MCP23017_1-GPA7)") (class "Default")
      (node (ref "MCP23017_1") (pin "28") (pinfunction "GPA7_28") (pintype "bidirectional"))
      (node (ref "R22") (pin "1") (pinfunction "1_1") (pintype "passive"))
    )
    (net (code "79") (name "Net-(MCP23017_1-GPB7)") (class "Default")
      (node (ref "MCP23017_1") (pin "8") (pinfunction "GPB7_8") (pintype "bidirectional"))
      (node (ref "R23") (pin "1") (pinfunction "1_1") (pintype "passive"))
    )
    (net (code "80") (name "Net-(MCP23017_1-~{RESET})") (class "Default")
      (node (ref "MCP23017_1") (pin "18") (pinfunction "~{RESET}_18") (pintype "input"))
      (node (ref "R35") (pin "2") (pinfunction "2_2") (pintype "passive"))
    )
    (net (code "81") (name "Net-(MCP23017_2-GPA0)") (class "Default")
      (node (ref "MCP23017_2") (pin "21") (pinfunction "GPA0_21") (pintype "bidirectional"))
      (node (ref "R4") (pin "1") (pinfunction "1_1") (pintype "passive"))
    )
    (net (code "82") (name "Net-(MCP23017_2-GPA1)") (class "Default")
      (node (ref "MCP23017_2") (pin "22") (pinfunction "GPA1_22") (pintype "bidirectional"))
      (node (ref "R5") (pin "1") (pinfunction "1_1") (pintype "passive"))
    )
    (net (code "83") (name "Net-(MCP23017_2-GPA2)") (class "Default")
      (node (ref "MCP23017_2") (pin "23") (pinfunction "GPA2_23") (pintype "bidirectional"))
      (node (ref "R6") (pin "1") (pinfunction "1_1") (pintype "passive"))
    )
    (net (code "84") (name "Net-(MCP23017_2-GPA3)") (class "Default")
      (node (ref "MCP23017_2") (pin "24") (pinfunction "GPA3_24") (pintype "bidirectional"))
      (node (ref "R7") (pin "1") (pinfunction "1_1") (pintype "passive"))
    )
    (net (code "85") (name "Net-(MCP23017_2-GPA4)") (class "Default")
      (node (ref "MCP23017_2") (pin "25") (pinfunction "GPA4_25") (pintype "bidirectional"))
      (node (ref "R8") (pin "1") (pinfunction "1_1") (pintype "passive"))
    )
    (net (code "86") (name "Net-(MCP23017_2-GPA5)") (class "Default")
      (node (ref "MCP23017_2") (pin "26") (pinfunction "GPA5_26") (pintype "bidirectional"))
      (node (ref "R9") (pin "1") (pinfunction "1_1") (pintype "passive"))
    )
    (net (code "87") (name "Net-(MCP23017_2-GPA6)") (class "Default")
      (node (ref "MCP23017_2") (pin "27") (pinfunction "GPA6_27") (pintype "bidirectional"))
      (node (ref "R10") (pin "1") (pinfunction "1_1") (pintype "passive"))
    )
    (net (code "88") (name "Net-(MCP23017_2-GPA7)") (class "Default")
      (node (ref "MCP23017_2") (pin "28") (pinfunction "GPA7_28") (pintype "bidirectional"))
      (node (ref "R11") (pin "1") (pinfunction "1_1") (pintype "passive"))
    )
    (net (code "89") (name "Net-(MCP23017_2-GPB0)") (class "Default")
      (node (ref "MCP23017_2") (pin "1") (pinfunction "GPB0_1") (pintype "bidirectional"))
      (node (ref "R1") (pin "1") (pinfunction "1_1") (pintype "passive"))
    )
    (net (code "90") (name "Net-(MCP23017_2-GPB1)") (class "Default")
      (node (ref "MCP23017_2") (pin "2") (pinfunction "GPB1_2") (pintype "bidirectional"))
      (node (ref "R2") (pin "1") (pinfunction "1_1") (pintype "passive"))
    )
    (net (code "91") (name "Net-(MCP23017_2-GPB2)") (class "Default")
      (node (ref "MCP23017_2") (pin "3") (pinfunction "GPB2_3") (pintype "bidirectional"))
      (node (ref "R3") (pin "1") (pinfunction "1_1") (pintype "passive"))
    )
    (net (code "92") (name "Net-(MCP23017_2-GPB7)") (class "Default")
      (node (ref "MCP23017_2") (pin "8") (pinfunction "GPB7_8") (pintype "bidirectional"))
      (node (ref "R12") (pin "1") (pinfunction "1_1") (pintype "passive"))
    )
    (net (code "93") (name "Net-(MCP23017_2-~{RESET})") (class "Default")
      (node (ref "MCP23017_2") (pin "18") (pinfunction "~{RESET}_18") (pintype "input"))
      (node (ref "R34") (pin "2") (pinfunction "2_2") (pintype "passive"))
    )
    (net (code "94") (name "unconnected-(ADX345--1-PadA1)") (class "Default")
      (node (ref "ADX345") (pin "A1") (pinfunction "-1_A1") (pintype "passive"))
    )
    (net (code "95") (name "unconnected-(ADX345--2-PadA2)") (class "Default")
      (node (ref "ADX345") (pin "A2") (pinfunction "-2_A2") (pintype "passive"))
    )
    (net (code "96") (name "unconnected-(ADX345--3-PadA3)") (class "Default")
      (node (ref "ADX345") (pin "A3") (pinfunction "-3_A3") (pintype "passive"))
    )
    (net (code "97") (name "unconnected-(ADX345--4-PadA4)") (class "Default")
      (node (ref "ADX345") (pin "A4") (pinfunction "-4_A4") (pintype "passive"))
    )
    (net (code "98") (name "unconnected-(FRISCHWASSERTANK--1-PadA1)") (class "Default")
      (node (ref "FRISCHWASSERTANK") (pin "A1") (pinfunction "-1_A1") (pintype "passive"))
    )
    (net (code "99") (name "unconnected-(FRISCHWASSERTANK--2-PadA2)") (class "Default")
      (node (ref "FRISCHWASSERTANK") (pin "A2") (pinfunction "-2_A2") (pintype "passive"))
    )
    (net (code "100") (name "unconnected-(FRISCHWASSERTANK--3-PadA3)") (class "Default")
      (node (ref "FRISCHWASSERTANK") (pin "A3") (pinfunction "-3_A3") (pintype "passive"))
    )
    (net (code "101") (name "unconnected-(FRISCHWASSERTANK--4-PadA4)") (class "Default")
      (node (ref "FRISCHWASSERTANK") (pin "A4") (pinfunction "-4_A4") (pintype "passive"))
    )
    (net (code "102") (name "unconnected-(FRISCHWASSERTANK--5-PadA5)") (class "Default")
      (node (ref "FRISCHWASSERTANK") (pin "A5") (pinfunction "-5_A5") (pintype "passive"))
    )
    (net (code "103") (name "unconnected-(FRISCHWASSERTANK--6-PadA6)") (class "Default")
      (node (ref "FRISCHWASSERTANK") (pin "A6") (pinfunction "-6_A6") (pintype "passive"))
    )
    (net (code "104") (name "unconnected-(FRISCHWASSERTANK--7-PadA7)") (class "Default")
      (node (ref "FRISCHWASSERTANK") (pin "A7") (pinfunction "-7_A7") (pintype "passive"))
    )
    (net (code "105") (name "unconnected-(FRISCHWASSERTANK--8-PadA8)") (class "Default")
      (node (ref "FRISCHWASSERTANK") (pin "A8") (pinfunction "-8_A8") (pintype "passive"))
    )
    (net (code "106") (name "unconnected-(FÄKALIENTANK--1-PadA1)") (class "Default")
      (node (ref "FÄKALIENTANK") (pin "A1") (pinfunction "-1_A1") (pintype "passive"))
    )
    (net (code "107") (name "unconnected-(FÄKALIENTANK--2-PadA2)") (class "Default")
      (node (ref "FÄKALIENTANK") (pin "A2") (pinfunction "-2_A2") (pintype "passive"))
    )
    (net (code "108") (name "unconnected-(FÄKALIENTANK--3-PadA3)") (class "Default")
      (node (ref "FÄKALIENTANK") (pin "A3") (pinfunction "-3_A3") (pintype "passive"))
    )
    (net (code "109") (name "unconnected-(FÄKALIENTANK--4-PadA4)") (class "Default")
      (node (ref "FÄKALIENTANK") (pin "A4") (pinfunction "-4_A4") (pintype "passive"))
    )
    (net (code "110") (name "unconnected-(FÄKALIENTANK--5-PadA5)") (class "Default")
      (node (ref "FÄKALIENTANK") (pin "A5") (pinfunction "-5_A5") (pintype "passive"))
    )
    (net (code "111") (name "unconnected-(FÄKALIENTANK--6-PadA6)") (class "Default")
      (node (ref "FÄKALIENTANK") (pin "A6") (pinfunction "-6_A6") (pintype "passive"))
    )
    (net (code "112") (name "unconnected-(FÄKALIENTANK--7-PadA7)") (class "Default")
      (node (ref "FÄKALIENTANK") (pin "A7") (pinfunction "-7_A7") (pintype "passive"))
    )
    (net (code "113") (name "unconnected-(FÄKALIENTANK--8-PadA8)") (class "Default")
      (node (ref "FÄKALIENTANK") (pin "A8") (pinfunction "-8_A8") (pintype "passive"))
    )
    (net (code "114") (name "unconnected-(FÄKALIENTANK-B-7-PadB7)") (class "Default")
      (node (ref "FÄKALIENTANK") (pin "B7") (pinfunction "B-7_B7") (pintype "passive"))
    )
    (net (code "115") (name "unconnected-(FÄKALIENTANK-B-8-PadB8)") (class "Default")
      (node (ref "FÄKALIENTANK") (pin "B8") (pinfunction "B-8_B8") (pintype "passive"))
    )
    (net (code "116") (name "unconnected-(GASWAAGE--1-PadA1)") (class "Default")
      (node (ref "GASWAAGE") (pin "A1") (pinfunction "-1_A1") (pintype "passive"))
    )
    (net (code "117") (name "unconnected-(GASWAAGE--2-PadA2)") (class "Default")
      (node (ref "GASWAAGE") (pin "A2") (pinfunction "-2_A2") (pintype "passive"))
    )
    (net (code "118") (name "unconnected-(GASWAAGE--3-PadA3)") (class "Default")
      (node (ref "GASWAAGE") (pin "A3") (pinfunction "-3_A3") (pintype "passive"))
    )
    (net (code "119") (name "unconnected-(GASWAAGE--4-PadA4)") (class "Default")
      (node (ref "GASWAAGE") (pin "A4") (pinfunction "-4_A4") (pintype "passive"))
    )
    (net (code "120") (name "unconnected-(GEHÄUSEDECKEL-Pad4)") (class "Default")
      (node (ref "GEHÄUSEDECKEL") (pin "4") (pinfunction "4_4") (pintype "passive"))
    )
    (net (code "121") (name "unconnected-(GEHÄUSEDECKEL-Pad6)") (class "Default")
      (node (ref "GEHÄUSEDECKEL") (pin "6") (pinfunction "6_6") (pintype "passive"))
    )
    (net (code "122") (name "unconnected-(GEHÄUSEDECKEL-Pad8)") (class "Default")
      (node (ref "GEHÄUSEDECKEL") (pin "8") (pinfunction "8_8") (pintype "passive"))
    )
    (net (code "123") (name "unconnected-(GEHÄUSEDECKEL-Pad10)") (class "Default")
      (node (ref "GEHÄUSEDECKEL") (pin "10") (pinfunction "10_10") (pintype "passive"))
    )
    (net (code "124") (name "unconnected-(GEHÄUSEDECKEL-Pad12)") (class "Default")
      (node (ref "GEHÄUSEDECKEL") (pin "12") (pinfunction "12_12") (pintype "passive"))
    )
    (net (code "125") (name "unconnected-(GPIO_EXTENSION--1-PadA1)") (class "Default")
      (node (ref "GPIO_EXTENSION") (pin "A1") (pinfunction "-1_A1") (pintype "passive"))
    )
    (net (code "126") (name "unconnected-(GPIO_EXTENSION--2-PadA2)") (class "Default")
      (node (ref "GPIO_EXTENSION") (pin "A2") (pinfunction "-2_A2") (pintype "passive"))
    )
    (net (code "127") (name "unconnected-(GPIO_EXTENSION--3-PadA3)") (class "Default")
      (node (ref "GPIO_EXTENSION") (pin "A3") (pinfunction "-3_A3") (pintype "passive"))
    )
    (net (code "128") (name "unconnected-(GPIO_EXTENSION--4-PadA4)") (class "Default")
      (node (ref "GPIO_EXTENSION") (pin "A4") (pinfunction "-4_A4") (pintype "passive"))
    )
    (net (code "129") (name "unconnected-(GPIO_EXTENSION--5-PadA5)") (class "Default")
      (node (ref "GPIO_EXTENSION") (pin "A5") (pinfunction "-5_A5") (pintype "passive"))
    )
    (net (code "130") (name "unconnected-(GPIO_EXTENSION--6-PadA6)") (class "Default")
      (node (ref "GPIO_EXTENSION") (pin "A6") (pinfunction "-6_A6") (pintype "passive"))
    )
    (net (code "131") (name "unconnected-(GPIO_EXTENSION--7-PadA7)") (class "Default")
      (node (ref "GPIO_EXTENSION") (pin "A7") (pinfunction "-7_A7") (pintype "passive"))
    )
    (net (code "132") (name "unconnected-(GPIO_EXTENSION--8-PadA8)") (class "Default")
      (node (ref "GPIO_EXTENSION") (pin "A8") (pinfunction "-8_A8") (pintype "passive"))
    )
    (net (code "133") (name "unconnected-(GPIO_EXTENSION--9-PadA9)") (class "Default")
      (node (ref "GPIO_EXTENSION") (pin "A9") (pinfunction "-9_A9") (pintype "passive"))
    )
    (net (code "134") (name "unconnected-(GPIO_EXTENSION--10-PadA10)") (class "Default")
      (node (ref "GPIO_EXTENSION") (pin "A10") (pinfunction "-10_A10") (pintype "passive"))
    )
    (net (code "135") (name "unconnected-(GPIO_EXTENSION--11-PadA11)") (class "Default")
      (node (ref "GPIO_EXTENSION") (pin "A11") (pinfunction "-11_A11") (pintype "passive"))
    )
    (net (code "136") (name "unconnected-(GPIO_EXTENSION--12-PadA12)") (class "Default")
      (node (ref "GPIO_EXTENSION") (pin "A12") (pinfunction "-12_A12") (pintype "passive"))
    )
    (net (code "137") (name "unconnected-(GPIO_EXTENSION--13-PadA13)") (class "Default")
      (node (ref "GPIO_EXTENSION") (pin "A13") (pinfunction "-13_A13") (pintype "passive"))
    )
    (net (code "138") (name "unconnected-(GPIO_EXTENSION--14-PadA14)") (class "Default")
      (node (ref "GPIO_EXTENSION") (pin "A14") (pinfunction "-14_A14") (pintype "passive"))
    )
    (net (code "139") (name "unconnected-(GPIO_EXTENSION--15-PadA15)") (class "Default")
      (node (ref "GPIO_EXTENSION") (pin "A15") (pinfunction "-15_A15") (pintype "passive"))
    )
    (net (code "140") (name "unconnected-(GPIO_EXTENSION--16-PadA16)") (class "Default")
      (node (ref "GPIO_EXTENSION") (pin "A16") (pinfunction "-16_A16") (pintype "passive"))
    )
    (net (code "141") (name "unconnected-(HX711-EXTERN--1-PadA1)") (class "Default")
      (node (ref "HX711-EXTERN") (pin "A1") (pinfunction "-1_A1") (pintype "passive"))
    )
    (net (code "142") (name "unconnected-(HX711-EXTERN--2-PadA2)") (class "Default")
      (node (ref "HX711-EXTERN") (pin "A2") (pinfunction "-2_A2") (pintype "passive"))
    )
    (net (code "143") (name "unconnected-(HX711-EXTERN--3-PadA3)") (class "Default")
      (node (ref "HX711-EXTERN") (pin "A3") (pinfunction "-3_A3") (pintype "passive"))
    )
    (net (code "144") (name "unconnected-(HX711-EXTERN--4-PadA4)") (class "Default")
      (node (ref "HX711-EXTERN") (pin "A4") (pinfunction "-4_A4") (pintype "passive"))
    )
    (net (code "145") (name "unconnected-(HX711-PadB+)") (class "Default")
      (node (ref "HX711") (pin "B+") (pinfunction "B+_B+") (pintype "bidirectional"))
    )
    (net (code "146") (name "unconnected-(HX711-PadB-)") (class "Default")
      (node (ref "HX711") (pin "B-") (pinfunction "B-_B-") (pintype "bidirectional"))
    )
    (net (code "147") (name "unconnected-(I2C-EXTENSION-Pad2)") (class "Default")
      (node (ref "I2C-EXTENSION") (pin "2") (pinfunction "2_2") (pintype "passive"))
    )
    (net (code "148") (name "unconnected-(I2C-EXTENSION-Pad4)") (class "Default")
      (node (ref "I2C-EXTENSION") (pin "4") (pinfunction "4_4") (pintype "passive"))
    )
    (net (code "149") (name "unconnected-(I2C-EXTENSION-Pad6)") (class "Default")
      (node (ref "I2C-EXTENSION") (pin "6") (pinfunction "6_6") (pintype "passive"))
    )
    (net (code "150") (name "unconnected-(I2C-EXTENSION-Pad7)") (class "Default")
      (node (ref "I2C-EXTENSION") (pin "7") (pinfunction "7_7") (pintype "passive"))
    )
    (net (code "151") (name "unconnected-(I2C-EXTENSION-Pad8)") (class "Default")
      (node (ref "I2C-EXTENSION") (pin "8") (pinfunction "8_8") (pintype "passive"))
    )
    (net (code "152") (name "unconnected-(I2CEXTENDER1-N.C.-Pad5)") (class "Default")
      (node (ref "I2CEXTENDER1") (pin "5") (pinfunction "N.C._5") (pintype "no_connect"))
    )
    (net (code "153") (name "unconnected-(I2CEXTENDER1-N.C._2-Pad1)") (class "Default")
      (node (ref "I2CEXTENDER1") (pin "1") (pinfunction "N.C._2_1") (pintype "no_connect"))
    )
    (net (code "154") (name "unconnected-(I2CEXTENDER2-N.C.-Pad5)") (class "Default")
      (node (ref "I2CEXTENDER2") (pin "5") (pinfunction "N.C._5") (pintype "no_connect"))
    )
    (net (code "155") (name "unconnected-(I2CEXTENDER2-N.C._2-Pad1)") (class "Default")
      (node (ref "I2CEXTENDER2") (pin "1") (pinfunction "N.C._2_1") (pintype "no_connect"))
    )
    (net (code "156") (name "unconnected-(KLIMA1--1-PadA1)") (class "Default")
      (node (ref "KLIMA1") (pin "A1") (pinfunction "-1_A1") (pintype "passive"))
    )
    (net (code "157") (name "unconnected-(KLIMA1--2-PadA2)") (class "Default")
      (node (ref "KLIMA1") (pin "A2") (pinfunction "-2_A2") (pintype "passive"))
    )
    (net (code "158") (name "unconnected-(KLIMA1--3-PadA3)") (class "Default")
      (node (ref "KLIMA1") (pin "A3") (pinfunction "-3_A3") (pintype "passive"))
    )
    (net (code "159") (name "unconnected-(KLIMA1--4-PadA4)") (class "Default")
      (node (ref "KLIMA1") (pin "A4") (pinfunction "-4_A4") (pintype "passive"))
    )
    (net (code "160") (name "unconnected-(KLIMA2--1-PadA1)") (class "Default")
      (node (ref "KLIMA2") (pin "A1") (pinfunction "-1_A1") (pintype "passive"))
    )
    (net (code "161") (name "unconnected-(KLIMA2--2-PadA2)") (class "Default")
      (node (ref "KLIMA2") (pin "A2") (pinfunction "-2_A2") (pintype "passive"))
    )
    (net (code "162") (name "unconnected-(KLIMA2--3-PadA3)") (class "Default")
      (node (ref "KLIMA2") (pin "A3") (pinfunction "-3_A3") (pintype "passive"))
    )
    (net (code "163") (name "unconnected-(KLIMA2--4-PadA4)") (class "Default")
      (node (ref "KLIMA2") (pin "A4") (pinfunction "-4_A4") (pintype "passive"))
    )
    (net (code "164") (name "unconnected-(KüHLSCHR.--1-PadA1)") (class "Default")
      (node (ref "KüHLSCHR.") (pin "A1") (pinfunction "-1_A1") (pintype "passive"))
    )
    (net (code "165") (name "unconnected-(KüHLSCHR.--2-PadA2)") (class "Default")
      (node (ref "KüHLSCHR.") (pin "A2") (pinfunction "-2_A2") (pintype "passive"))
    )
    (net (code "166") (name "unconnected-(KüHLSCHR.--3-PadA3)") (class "Default")
      (node (ref "KüHLSCHR.") (pin "A3") (pinfunction "-3_A3") (pintype "passive"))
    )
    (net (code "167") (name "unconnected-(LED-HL--1-PadA1)") (class "Default")
      (node (ref "LED-HL") (pin "A1") (pinfunction "-1_A1") (pintype "passive"))
    )
    (net (code "168") (name "unconnected-(LED-HL--2-PadA2)") (class "Default")
      (node (ref "LED-HL") (pin "A2") (pinfunction "-2_A2") (pintype "passive"))
    )
    (net (code "169") (name "unconnected-(LED-HL--3-PadA3)") (class "Default")
      (node (ref "LED-HL") (pin "A3") (pinfunction "-3_A3") (pintype "passive"))
    )
    (net (code "170") (name "unconnected-(LED-HL--4-PadA4)") (class "Default")
      (node (ref "LED-HL") (pin "A4") (pinfunction "-4_A4") (pintype "passive"))
    )
    (net (code "171") (name "unconnected-(LED-HR--1-PadA1)") (class "Default")
      (node (ref "LED-HR") (pin "A1") (pinfunction "-1_A1") (pintype "passive"))
    )
    (net (code "172") (name "unconnected-(LED-HR--2-PadA2)") (class "Default")
      (node (ref "LED-HR") (pin "A2") (pinfunction "-2_A2") (pintype "passive"))
    )
    (net (code "173") (name "unconnected-(LED-HR--3-PadA3)") (class "Default")
      (node (ref "LED-HR") (pin "A3") (pinfunction "-3_A3") (pintype "passive"))
    )
    (net (code "174") (name "unconnected-(LED-HR--4-PadA4)") (class "Default")
      (node (ref "LED-HR") (pin "A4") (pinfunction "-4_A4") (pintype "passive"))
    )
    (net (code "175") (name "unconnected-(LED-VD--1-PadA1)") (class "Default")
      (node (ref "LED-VD") (pin "A1") (pinfunction "-1_A1") (pintype "passive"))
    )
    (net (code "176") (name "unconnected-(LED-VD--2-PadA2)") (class "Default")
      (node (ref "LED-VD") (pin "A2") (pinfunction "-2_A2") (pintype "passive"))
    )
    (net (code "177") (name "unconnected-(LED-VD--3-PadA3)") (class "Default")
      (node (ref "LED-VD") (pin "A3") (pinfunction "-3_A3") (pintype "passive"))
    )
    (net (code "178") (name "unconnected-(LED-VD--4-PadA4)") (class "Default")
      (node (ref "LED-VD") (pin "A4") (pinfunction "-4_A4") (pintype "passive"))
    )
    (net (code "179") (name "unconnected-(LED-VL--1-PadA1)") (class "Default")
      (node (ref "LED-VL") (pin "A1") (pinfunction "-1_A1") (pintype "passive"))
    )
    (net (code "180") (name "unconnected-(LED-VL--2-PadA2)") (class "Default")
      (node (ref "LED-VL") (pin "A2") (pinfunction "-2_A2") (pintype "passive"))
    )
    (net (code "181") (name "unconnected-(LED-VL--3-PadA3)") (class "Default")
      (node (ref "LED-VL") (pin "A3") (pinfunction "-3_A3") (pintype "passive"))
    )
    (net (code "182") (name "unconnected-(LED-VL--4-PadA4)") (class "Default")
      (node (ref "LED-VL") (pin "A4") (pinfunction "-4_A4") (pintype "passive"))
    )
    (net (code "183") (name "unconnected-(LED-VR--1-PadA1)") (class "Default")
      (node (ref "LED-VR") (pin "A1") (pinfunction "-1_A1") (pintype "passive"))
    )
    (net (code "184") (name "unconnected-(LED-VR--2-PadA2)") (class "Default")
      (node (ref "LED-VR") (pin "A2") (pinfunction "-2_A2") (pintype "passive"))
    )
    (net (code "185") (name "unconnected-(LED-VR--3-PadA3)") (class "Default")
      (node (ref "LED-VR") (pin "A3") (pinfunction "-3_A3") (pintype "passive"))
    )
    (net (code "186") (name "unconnected-(LED-VR--4-PadA4)") (class "Default")
      (node (ref "LED-VR") (pin "A4") (pinfunction "-4_A4") (pintype "passive"))
    )
    (net (code "187") (name "unconnected-(LED-ZL--1-PadA1)") (class "Default")
      (node (ref "LED-ZL") (pin "A1") (pinfunction "-1_A1") (pintype "passive"))
    )
    (net (code "188") (name "unconnected-(LED-ZL--2-PadA2)") (class "Default")
      (node (ref "LED-ZL") (pin "A2") (pinfunction "-2_A2") (pintype "passive"))
    )
    (net (code "189") (name "unconnected-(LED-ZL--3-PadA3)") (class "Default")
      (node (ref "LED-ZL") (pin "A3") (pinfunction "-3_A3") (pintype "passive"))
    )
    (net (code "190") (name "unconnected-(LED-ZL--4-PadA4)") (class "Default")
      (node (ref "LED-ZL") (pin "A4") (pinfunction "-4_A4") (pintype "passive"))
    )
    (net (code "191") (name "unconnected-(LED-ZR--1-PadA1)") (class "Default")
      (node (ref "LED-ZR") (pin "A1") (pinfunction "-1_A1") (pintype "passive"))
    )
    (net (code "192") (name "unconnected-(LED-ZR--2-PadA2)") (class "Default")
      (node (ref "LED-ZR") (pin "A2") (pinfunction "-2_A2") (pintype "passive"))
    )
    (net (code "193") (name "unconnected-(LED-ZR--3-PadA3)") (class "Default")
      (node (ref "LED-ZR") (pin "A3") (pinfunction "-3_A3") (pintype "passive"))
    )
    (net (code "194") (name "unconnected-(LED-ZR--4-PadA4)") (class "Default")
      (node (ref "LED-ZR") (pin "A4") (pinfunction "-4_A4") (pintype "passive"))
    )
    (net (code "195") (name "unconnected-(MCP23017_1-INTA-Pad20)") (class "Default")
      (node (ref "MCP23017_1") (pin "20") (pinfunction "INTA_20") (pintype "output"))
    )
    (net (code "196") (name "unconnected-(MCP23017_1-INTB-Pad19)") (class "Default")
      (node (ref "MCP23017_1") (pin "19") (pinfunction "INTB_19") (pintype "output"))
    )
    (net (code "197") (name "unconnected-(MCP23017_2-INTA-Pad20)") (class "Default")
      (node (ref "MCP23017_2") (pin "20") (pinfunction "INTA_20") (pintype "output"))
    )
    (net (code "198") (name "unconnected-(MCP23017_2-INTB-Pad19)") (class "Default")
      (node (ref "MCP23017_2") (pin "19") (pinfunction "INTB_19") (pintype "output"))
    )
    (net (code "199") (name "unconnected-(RADAR--1-PadA1)") (class "Default")
      (node (ref "RADAR") (pin "A1") (pinfunction "-1_A1") (pintype "passive"))
    )
    (net (code "200") (name "unconnected-(RADAR--2-PadA2)") (class "Default")
      (node (ref "RADAR") (pin "A2") (pinfunction "-2_A2") (pintype "passive"))
    )
    (net (code "201") (name "unconnected-(RADAR--3-PadA3)") (class "Default")
      (node (ref "RADAR") (pin "A3") (pinfunction "-3_A3") (pintype "passive"))
    )
    (net (code "202") (name "unconnected-(RASPBERRY-PI-Pad10)") (class "Default")
      (node (ref "RASPBERRY-PI") (pin "10") (pinfunction "10_10") (pintype "passive"))
    )
  )
)
